# Motor_Power.net
KiCad netlist of a schematic drawn in Altium Designer
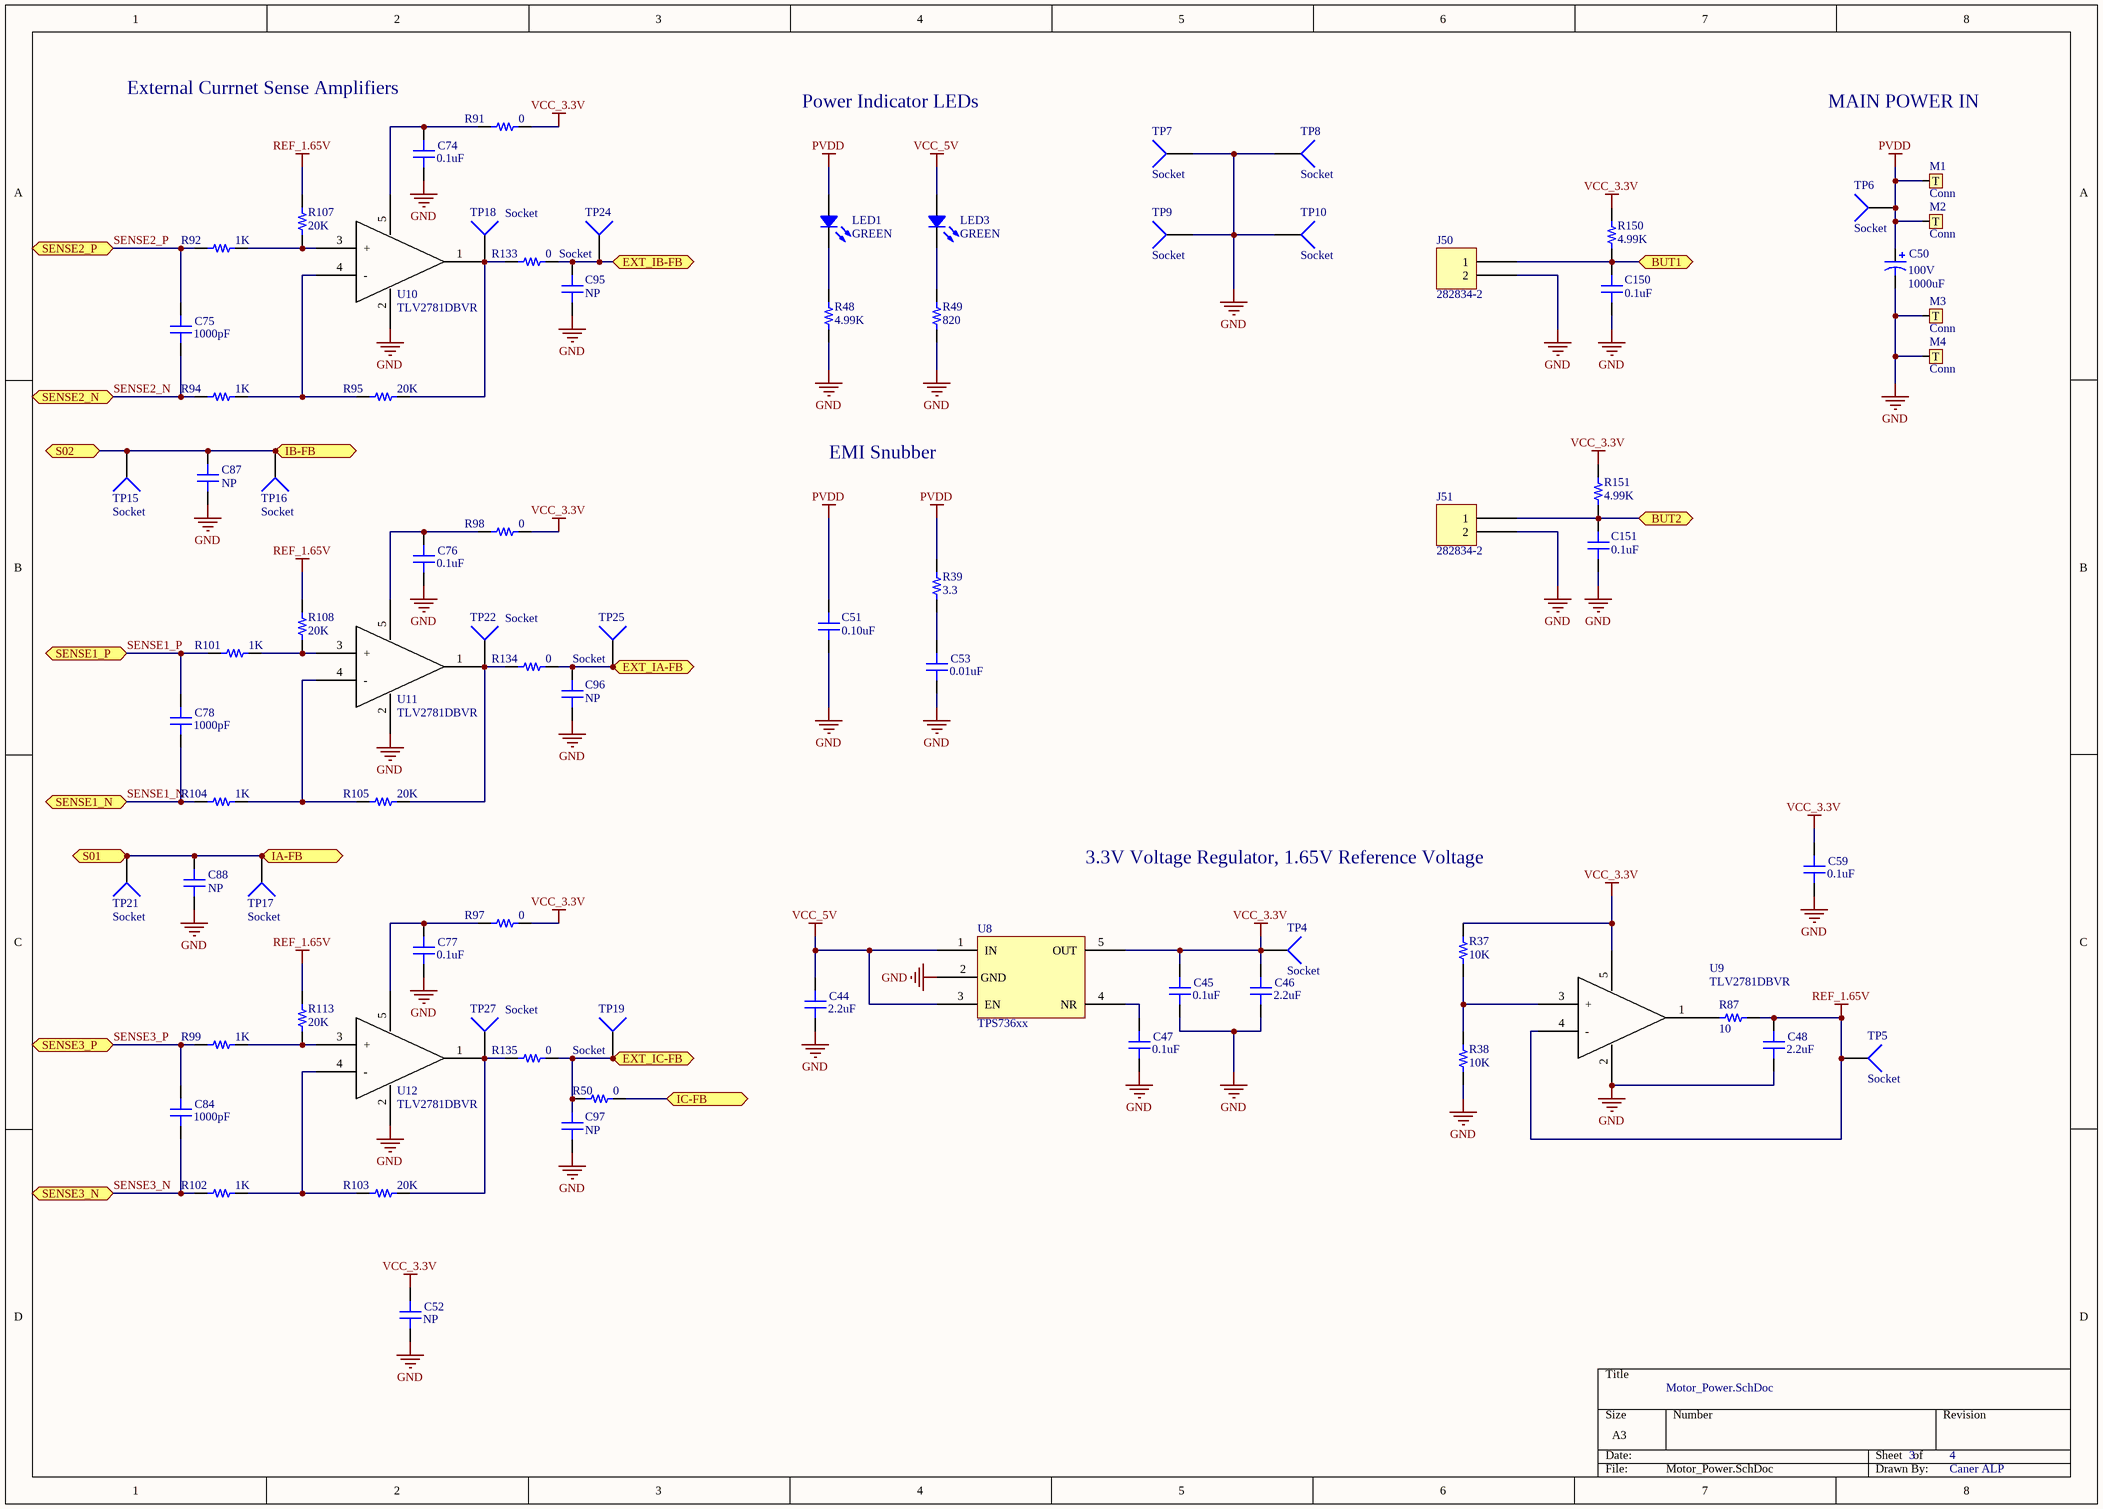
[diagram p0: Motor_Power.SchDoc]

(export (version "E")
  (design (tool "Eeschema 10.0.6"))
  (components
    (comp (ref "C44")
      (value "2.2uF")
      (footprint "CAP 0603/1608")
      (description "CAP CER 0.1UF 16V X7R 0603")
      (fields (field (name "PART NUMBER") "CC0603KPX7R7BB104") (field (name "MANUFACTURER") "Yageo"))
      (libsource (lib "Celestial Library Database") (part "Capacitor"))
    )
    (comp (ref "C45")
      (value "0.1uF")
      (footprint "CAP 0603/1608")
      (description "CAP CER 0.1UF 16V X7R 0603")
      (fields (field (name "PART NUMBER") "CC0603KPX7R7BB104") (field (name "MANUFACTURER") "Yageo"))
      (libsource (lib "Celestial Library Database") (part "Capacitor"))
    )
    (comp (ref "C46")
      (value "2.2uF")
      (footprint "CAP 0603/1608")
      (description "CAP CER 0.1UF 16V X7R 0603")
      (fields (field (name "PART NUMBER") "CC0603KPX7R7BB104") (field (name "MANUFACTURER") "Yageo"))
      (libsource (lib "Celestial Library Database") (part "Capacitor"))
    )
    (comp (ref "C47")
      (value "0.1uF")
      (footprint "CAP 0603/1608")
      (description "CAP CER 0.1UF 16V X7R 0603")
      (fields (field (name "PART NUMBER") "CC0603KPX7R7BB104") (field (name "MANUFACTURER") "Yageo"))
      (libsource (lib "Celestial Library Database") (part "Capacitor"))
    )
    (comp (ref "C48")
      (value "2.2uF")
      (footprint "CAP 0603/1608")
      (description "CAP CER 0.1UF 16V X7R 0603")
      (fields (field (name "PART NUMBER") "CC0603KPX7R7BB104") (field (name "MANUFACTURER") "Yageo"))
      (libsource (lib "Celestial Library Database") (part "Capacitor"))
    )
    (comp (ref "C50")
      (value "100V")
      (footprint "CAPPR7.5-18x35.5")
      (description "Polarized Capacitor (Radial)")
      (fields (field (name "ALTIUM_VALUE") "1000uF") (field (name "PUBLISHER") "Altium Limited"))
      (libsource (lib "Miscellaneous Devices") (part "Cap Pol1"))
    )
    (comp (ref "C51")
      (value "0.10uF")
      (footprint "CAP 0805/2012")
      (description "CAP CER 0.1UF 100V X7R 0805")
      (fields (field (name "PART NUMBER") "C0805C104K1RACTU") (field (name "MANUFACTURER") "Kemet"))
      (libsource (lib "Celestial Library Database") (part "Capacitor"))
    )
    (comp (ref "C52")
      (value "NP")
      (footprint "CAP 0603/1608")
      (description "CAP CER 0.1UF 16V X7R 0603")
      (fields (field (name "PART NUMBER") "CC0603KPX7R7BB104") (field (name "MANUFACTURER") "Yageo"))
      (libsource (lib "Celestial Library Database") (part "Capacitor"))
    )
    (comp (ref "C53")
      (value "0.01uF")
      (footprint "CAP 0603/1608")
      (description "CAP CER 0.1UF 16V X7R 0603")
      (fields (field (name "PART NUMBER") "CC0603KPX7R7BB104") (field (name "MANUFACTURER") "Yageo"))
      (libsource (lib "Celestial Library Database") (part "Capacitor"))
    )
    (comp (ref "C59")
      (value "0.1uF")
      (footprint "CAP 0603/1608")
      (description "CAP CER 0.1UF 16V X7R 0603")
      (fields (field (name "PART NUMBER") "CC0603KPX7R7BB104") (field (name "MANUFACTURER") "Yageo"))
      (libsource (lib "Celestial Library Database") (part "Capacitor"))
    )
    (comp (ref "C74")
      (value "0.1uF")
      (footprint "CAP 0603/1608")
      (description "CAP CER 0.1UF 16V X7R 0603")
      (fields (field (name "PART NUMBER") "CC0603KPX7R7BB104") (field (name "MANUFACTURER") "Yageo"))
      (libsource (lib "Celestial Library Database") (part "Capacitor"))
    )
    (comp (ref "C75")
      (value "1000pF")
      (footprint "CAP 0603/1608")
      (description "CAP CER 0.1UF 16V X7R 0603")
      (fields (field (name "PART NUMBER") "CC0603KPX7R7BB104") (field (name "MANUFACTURER") "Yageo"))
      (libsource (lib "Celestial Library Database") (part "Capacitor"))
    )
    (comp (ref "C76")
      (value "0.1uF")
      (footprint "CAP 0603/1608")
      (description "CAP CER 0.1UF 16V X7R 0603")
      (fields (field (name "PART NUMBER") "CC0603KPX7R7BB104") (field (name "MANUFACTURER") "Yageo"))
      (libsource (lib "Celestial Library Database") (part "Capacitor"))
    )
    (comp (ref "C77")
      (value "0.1uF")
      (footprint "CAP 0603/1608")
      (description "CAP CER 0.1UF 16V X7R 0603")
      (fields (field (name "PART NUMBER") "CC0603KPX7R7BB104") (field (name "MANUFACTURER") "Yageo"))
      (libsource (lib "Celestial Library Database") (part "Capacitor"))
    )
    (comp (ref "C78")
      (value "1000pF")
      (footprint "CAP 0603/1608")
      (description "CAP CER 0.1UF 16V X7R 0603")
      (fields (field (name "PART NUMBER") "CC0603KPX7R7BB104") (field (name "MANUFACTURER") "Yageo"))
      (libsource (lib "Celestial Library Database") (part "Capacitor"))
    )
    (comp (ref "C84")
      (value "1000pF")
      (footprint "CAP 0603/1608")
      (description "CAP CER 0.1UF 16V X7R 0603")
      (fields (field (name "PART NUMBER") "CC0603KPX7R7BB104") (field (name "MANUFACTURER") "Yageo"))
      (libsource (lib "Celestial Library Database") (part "Capacitor"))
    )
    (comp (ref "C87")
      (value "NP")
      (footprint "CAP 0603/1608")
      (description "CAP CER 0.1UF 16V X7R 0603")
      (fields (field (name "PART NUMBER") "CC0603KPX7R7BB104") (field (name "MANUFACTURER") "Yageo"))
      (libsource (lib "Celestial Library Database") (part "Capacitor"))
    )
    (comp (ref "C88")
      (value "NP")
      (footprint "CAP 0603/1608")
      (description "CAP CER 0.1UF 16V X7R 0603")
      (fields (field (name "PART NUMBER") "CC0603KPX7R7BB104") (field (name "MANUFACTURER") "Yageo"))
      (libsource (lib "Celestial Library Database") (part "Capacitor"))
    )
    (comp (ref "C95")
      (value "NP")
      (footprint "CAP 0603/1608")
      (description "CAP CER 0.1UF 16V X7R 0603")
      (fields (field (name "PART NUMBER") "CC0603KPX7R7BB104") (field (name "MANUFACTURER") "Yageo"))
      (libsource (lib "Celestial Library Database") (part "Capacitor"))
    )
    (comp (ref "C96")
      (value "NP")
      (footprint "CAP 0603/1608")
      (description "CAP CER 0.1UF 16V X7R 0603")
      (fields (field (name "PART NUMBER") "CC0603KPX7R7BB104") (field (name "MANUFACTURER") "Yageo"))
      (libsource (lib "Celestial Library Database") (part "Capacitor"))
    )
    (comp (ref "C97")
      (value "NP")
      (footprint "CAP 0603/1608")
      (description "CAP CER 0.1UF 16V X7R 0603")
      (fields (field (name "PART NUMBER") "CC0603KPX7R7BB104") (field (name "MANUFACTURER") "Yageo"))
      (libsource (lib "Celestial Library Database") (part "Capacitor"))
    )
    (comp (ref "C150")
      (value "0.1uF")
      (footprint "CAP 0603/1608")
      (description "CAP CER 0.1UF 16V X7R 0603")
      (fields (field (name "PART NUMBER") "CC0603KPX7R7BB104") (field (name "MANUFACTURER") "Yageo"))
      (libsource (lib "Celestial Library Database") (part "Capacitor"))
    )
    (comp (ref "C151")
      (value "0.1uF")
      (footprint "CAP 0603/1608")
      (description "CAP CER 0.1UF 16V X7R 0603")
      (fields (field (name "PART NUMBER") "CC0603KPX7R7BB104") (field (name "MANUFACTURER") "Yageo"))
      (libsource (lib "Celestial Library Database") (part "Capacitor"))
    )
    (comp (ref "J50")
      (value "282834-2")
      (footprint "TE 282834-2")
      (description "TERM BLOCK 2POS SIDE ENT 2.54MM")
      (fields (field (name "MANUFACTURER") "TE Connectivity AMP Connectors") (field (name "VOLTAGE") "150V"))
      (libsource (lib "Celestial Library Database") (part "2 Pin"))
    )
    (comp (ref "J51")
      (value "282834-2")
      (footprint "TE 282834-2")
      (description "TERM BLOCK 2POS SIDE ENT 2.54MM")
      (fields (field (name "MANUFACTURER") "TE Connectivity AMP Connectors") (field (name "VOLTAGE") "150V"))
      (libsource (lib "Celestial Library Database") (part "2 Pin"))
    )
    (comp (ref "LED1")
      (value "GREEN")
      (footprint "LED 0805/2012 YELLOW")
      (description "LED ORANGE CLEAR 0805 SMD")
      (fields (field (name "PART NUMBER") "LTST-C170KFKT") (field (name "MANUFACTURER") "Lite-On Inc."))
      (libsource (lib "Celestial Library Database") (part "LED"))
    )
    (comp (ref "LED3")
      (value "GREEN")
      (footprint "LED 0805/2012 YELLOW")
      (description "LED ORANGE CLEAR 0805 SMD")
      (fields (field (name "PART NUMBER") "LTST-C170KFKT") (field (name "MANUFACTURER") "Lite-On Inc."))
      (libsource (lib "Celestial Library Database") (part "LED"))
    )
    (comp (ref "M1") (value "Conn") (footprint "M5 Nut") (libsource (lib "Altium Component") (part "1 Conn")))
    (comp (ref "M2") (value "Conn") (footprint "M5 Nut") (libsource (lib "Altium Component") (part "1 Conn")))
    (comp (ref "M3") (value "Conn") (footprint "M5 Nut") (libsource (lib "Altium Component") (part "1 Conn")))
    (comp (ref "M4") (value "Conn") (footprint "M5 Nut") (libsource (lib "Altium Component") (part "1 Conn")))
    (comp (ref "R37")
      (value "10K")
      (footprint "RES 0603/1608")
      (description "RES SMD 330 OHM 5% 1/10W 0603")
      (fields
        (field (name "PART NUMBER") "ERJ-3GEYJ331V")
        (field (name "MANUFACTURER") "Panasonic Electronic Components")
      )
      (libsource (lib "Celestial Library Database") (part "Resistor"))
    )
    (comp (ref "R38")
      (value "10K")
      (footprint "RES 0603/1608")
      (description "RES SMD 330 OHM 5% 1/10W 0603")
      (fields
        (field (name "PART NUMBER") "ERJ-3GEYJ331V")
        (field (name "MANUFACTURER") "Panasonic Electronic Components")
      )
      (libsource (lib "Celestial Library Database") (part "Resistor"))
    )
    (comp (ref "R39")
      (value "3.3")
      (footprint "RES 1206/3216")
      (description "RES SMD 3.3 OHM 5% 1/4W 1206")
      (fields
        (field (name "PART NUMBER") "ERJ-8GEYJ3R3V")
        (field (name "MANUFACTURER") "Panasonic Electronic Components")
      )
      (libsource (lib "Celestial Library Database") (part "Resistor"))
    )
    (comp (ref "R48")
      (value "4.99K")
      (footprint "RES 0603/1608")
      (description "RES SMD 330 OHM 5% 1/10W 0603")
      (fields
        (field (name "PART NUMBER") "ERJ-3GEYJ331V")
        (field (name "MANUFACTURER") "Panasonic Electronic Components")
      )
      (libsource (lib "Celestial Library Database") (part "Resistor"))
    )
    (comp (ref "R49")
      (value "820")
      (footprint "RES 0603/1608")
      (description "RES SMD 330 OHM 5% 1/10W 0603")
      (fields
        (field (name "PART NUMBER") "ERJ-3GEYJ331V")
        (field (name "MANUFACTURER") "Panasonic Electronic Components")
      )
      (libsource (lib "Celestial Library Database") (part "Resistor"))
    )
    (comp (ref "R50")
      (value "0")
      (footprint "RES 0603/1608")
      (description "RES SMD 330 OHM 5% 1/10W 0603")
      (fields
        (field (name "PART NUMBER") "ERJ-3GEYJ331V")
        (field (name "MANUFACTURER") "Panasonic Electronic Components")
      )
      (libsource (lib "Celestial Library Database") (part "Resistor"))
    )
    (comp (ref "R87")
      (value "10")
      (footprint "RES 0603/1608")
      (description "RES SMD 330 OHM 5% 1/10W 0603")
      (fields
        (field (name "PART NUMBER") "ERJ-3GEYJ331V")
        (field (name "MANUFACTURER") "Panasonic Electronic Components")
      )
      (libsource (lib "Celestial Library Database") (part "Resistor"))
    )
    (comp (ref "R91")
      (value "0")
      (footprint "RES 0603/1608")
      (description "RES SMD 330 OHM 5% 1/10W 0603")
      (fields
        (field (name "PART NUMBER") "ERJ-3GEYJ331V")
        (field (name "MANUFACTURER") "Panasonic Electronic Components")
      )
      (libsource (lib "Celestial Library Database") (part "Resistor"))
    )
    (comp (ref "R92")
      (value "1K")
      (footprint "RES 0603/1608")
      (description "RES SMD 330 OHM 5% 1/10W 0603")
      (fields
        (field (name "PART NUMBER") "ERJ-3GEYJ331V")
        (field (name "MANUFACTURER") "Panasonic Electronic Components")
      )
      (libsource (lib "Celestial Library Database") (part "Resistor"))
    )
    (comp (ref "R94")
      (value "1K")
      (footprint "RES 0603/1608")
      (description "RES SMD 330 OHM 5% 1/10W 0603")
      (fields
        (field (name "PART NUMBER") "ERJ-3GEYJ331V")
        (field (name "MANUFACTURER") "Panasonic Electronic Components")
      )
      (libsource (lib "Celestial Library Database") (part "Resistor"))
    )
    (comp (ref "R95")
      (value "20K")
      (footprint "RES 0603/1608")
      (description "RES SMD 330 OHM 5% 1/10W 0603")
      (fields
        (field (name "PART NUMBER") "ERJ-3GEYJ331V")
        (field (name "MANUFACTURER") "Panasonic Electronic Components")
      )
      (libsource (lib "Celestial Library Database") (part "Resistor"))
    )
    (comp (ref "R97")
      (value "0")
      (footprint "RES 0603/1608")
      (description "RES SMD 330 OHM 5% 1/10W 0603")
      (fields
        (field (name "PART NUMBER") "ERJ-3GEYJ331V")
        (field (name "MANUFACTURER") "Panasonic Electronic Components")
      )
      (libsource (lib "Celestial Library Database") (part "Resistor"))
    )
    (comp (ref "R98")
      (value "0")
      (footprint "RES 0603/1608")
      (description "RES SMD 330 OHM 5% 1/10W 0603")
      (fields
        (field (name "PART NUMBER") "ERJ-3GEYJ331V")
        (field (name "MANUFACTURER") "Panasonic Electronic Components")
      )
      (libsource (lib "Celestial Library Database") (part "Resistor"))
    )
    (comp (ref "R99")
      (value "1K")
      (footprint "RES 0603/1608")
      (description "RES SMD 330 OHM 5% 1/10W 0603")
      (fields
        (field (name "PART NUMBER") "ERJ-3GEYJ331V")
        (field (name "MANUFACTURER") "Panasonic Electronic Components")
      )
      (libsource (lib "Celestial Library Database") (part "Resistor"))
    )
    (comp (ref "R101")
      (value "1K")
      (footprint "RES 0603/1608")
      (description "RES SMD 330 OHM 5% 1/10W 0603")
      (fields
        (field (name "PART NUMBER") "ERJ-3GEYJ331V")
        (field (name "MANUFACTURER") "Panasonic Electronic Components")
      )
      (libsource (lib "Celestial Library Database") (part "Resistor"))
    )
    (comp (ref "R102")
      (value "1K")
      (footprint "RES 0603/1608")
      (description "RES SMD 330 OHM 5% 1/10W 0603")
      (fields
        (field (name "PART NUMBER") "ERJ-3GEYJ331V")
        (field (name "MANUFACTURER") "Panasonic Electronic Components")
      )
      (libsource (lib "Celestial Library Database") (part "Resistor"))
    )
    (comp (ref "R103")
      (value "20K")
      (footprint "RES 0603/1608")
      (description "RES SMD 330 OHM 5% 1/10W 0603")
      (fields
        (field (name "PART NUMBER") "ERJ-3GEYJ331V")
        (field (name "MANUFACTURER") "Panasonic Electronic Components")
      )
      (libsource (lib "Celestial Library Database") (part "Resistor"))
    )
    (comp (ref "R104")
      (value "1K")
      (footprint "RES 0603/1608")
      (description "RES SMD 330 OHM 5% 1/10W 0603")
      (fields
        (field (name "PART NUMBER") "ERJ-3GEYJ331V")
        (field (name "MANUFACTURER") "Panasonic Electronic Components")
      )
      (libsource (lib "Celestial Library Database") (part "Resistor"))
    )
    (comp (ref "R105")
      (value "20K")
      (footprint "RES 0603/1608")
      (description "RES SMD 330 OHM 5% 1/10W 0603")
      (fields
        (field (name "PART NUMBER") "ERJ-3GEYJ331V")
        (field (name "MANUFACTURER") "Panasonic Electronic Components")
      )
      (libsource (lib "Celestial Library Database") (part "Resistor"))
    )
    (comp (ref "R107")
      (value "20K")
      (footprint "RES 0603/1608")
      (description "RES SMD 330 OHM 5% 1/10W 0603")
      (fields
        (field (name "PART NUMBER") "ERJ-3GEYJ331V")
        (field (name "MANUFACTURER") "Panasonic Electronic Components")
      )
      (libsource (lib "Celestial Library Database") (part "Resistor"))
    )
    (comp (ref "R108")
      (value "20K")
      (footprint "RES 0603/1608")
      (description "RES SMD 330 OHM 5% 1/10W 0603")
      (fields
        (field (name "PART NUMBER") "ERJ-3GEYJ331V")
        (field (name "MANUFACTURER") "Panasonic Electronic Components")
      )
      (libsource (lib "Celestial Library Database") (part "Resistor"))
    )
    (comp (ref "R113")
      (value "20K")
      (footprint "RES 0603/1608")
      (description "RES SMD 330 OHM 5% 1/10W 0603")
      (fields
        (field (name "PART NUMBER") "ERJ-3GEYJ331V")
        (field (name "MANUFACTURER") "Panasonic Electronic Components")
      )
      (libsource (lib "Celestial Library Database") (part "Resistor"))
    )
    (comp (ref "R133")
      (value "0")
      (footprint "RES 0603/1608")
      (description "RES SMD 330 OHM 5% 1/10W 0603")
      (fields
        (field (name "PART NUMBER") "ERJ-3GEYJ331V")
        (field (name "MANUFACTURER") "Panasonic Electronic Components")
      )
      (libsource (lib "Celestial Library Database") (part "Resistor"))
    )
    (comp (ref "R134")
      (value "0")
      (footprint "RES 0603/1608")
      (description "RES SMD 330 OHM 5% 1/10W 0603")
      (fields
        (field (name "PART NUMBER") "ERJ-3GEYJ331V")
        (field (name "MANUFACTURER") "Panasonic Electronic Components")
      )
      (libsource (lib "Celestial Library Database") (part "Resistor"))
    )
    (comp (ref "R135")
      (value "0")
      (footprint "RES 0603/1608")
      (description "RES SMD 330 OHM 5% 1/10W 0603")
      (fields
        (field (name "PART NUMBER") "ERJ-3GEYJ331V")
        (field (name "MANUFACTURER") "Panasonic Electronic Components")
      )
      (libsource (lib "Celestial Library Database") (part "Resistor"))
    )
    (comp (ref "R150")
      (value "4.99K")
      (footprint "RES 0603/1608")
      (description "RES SMD 330 OHM 5% 1/10W 0603")
      (fields
        (field (name "PART NUMBER") "ERJ-3GEYJ331V")
        (field (name "MANUFACTURER") "Panasonic Electronic Components")
      )
      (libsource (lib "Celestial Library Database") (part "Resistor"))
    )
    (comp (ref "R151")
      (value "4.99K")
      (footprint "RES 0603/1608")
      (description "RES SMD 330 OHM 5% 1/10W 0603")
      (fields
        (field (name "PART NUMBER") "ERJ-3GEYJ331V")
        (field (name "MANUFACTURER") "Panasonic Electronic Components")
      )
      (libsource (lib "Celestial Library Database") (part "Resistor"))
    )
    (comp (ref "TP4")
      (value "Socket")
      (footprint "PIN1")
      (fields (field (name "PUBLISHER") "Altium Limited"))
      (libsource (lib "Miscellaneous Connectors") (part "Socket"))
    )
    (comp (ref "TP5")
      (value "Socket")
      (footprint "PIN1")
      (fields (field (name "PUBLISHER") "Altium Limited"))
      (libsource (lib "Miscellaneous Connectors") (part "Socket"))
    )
    (comp (ref "TP6")
      (value "Socket")
      (footprint "PIN1")
      (fields (field (name "PUBLISHER") "Altium Limited"))
      (libsource (lib "Miscellaneous Connectors") (part "Socket"))
    )
    (comp (ref "TP7")
      (value "Socket")
      (footprint "PIN1")
      (fields (field (name "PUBLISHER") "Altium Limited"))
      (libsource (lib "Miscellaneous Connectors") (part "Socket"))
    )
    (comp (ref "TP8")
      (value "Socket")
      (footprint "PIN1")
      (fields (field (name "PUBLISHER") "Altium Limited"))
      (libsource (lib "Miscellaneous Connectors") (part "Socket"))
    )
    (comp (ref "TP9")
      (value "Socket")
      (footprint "PIN1")
      (fields (field (name "PUBLISHER") "Altium Limited"))
      (libsource (lib "Miscellaneous Connectors") (part "Socket"))
    )
    (comp (ref "TP10")
      (value "Socket")
      (footprint "PIN1")
      (fields (field (name "PUBLISHER") "Altium Limited"))
      (libsource (lib "Miscellaneous Connectors") (part "Socket"))
    )
    (comp (ref "TP15")
      (value "Socket")
      (footprint "PIN1")
      (fields (field (name "PUBLISHER") "Altium Limited"))
      (libsource (lib "Miscellaneous Connectors") (part "Socket"))
    )
    (comp (ref "TP16")
      (value "Socket")
      (footprint "PIN1")
      (fields (field (name "PUBLISHER") "Altium Limited"))
      (libsource (lib "Miscellaneous Connectors") (part "Socket"))
    )
    (comp (ref "TP17")
      (value "Socket")
      (footprint "PIN1")
      (fields (field (name "PUBLISHER") "Altium Limited"))
      (libsource (lib "Miscellaneous Connectors") (part "Socket"))
    )
    (comp (ref "TP18")
      (value "Socket")
      (footprint "PIN1")
      (fields (field (name "PUBLISHER") "Altium Limited"))
      (libsource (lib "Miscellaneous Connectors") (part "Socket"))
    )
    (comp (ref "TP19")
      (value "Socket")
      (footprint "PIN1")
      (fields (field (name "PUBLISHER") "Altium Limited"))
      (libsource (lib "Miscellaneous Connectors") (part "Socket"))
    )
    (comp (ref "TP21")
      (value "Socket")
      (footprint "PIN1")
      (fields (field (name "PUBLISHER") "Altium Limited"))
      (libsource (lib "Miscellaneous Connectors") (part "Socket"))
    )
    (comp (ref "TP22")
      (value "Socket")
      (footprint "PIN1")
      (fields (field (name "PUBLISHER") "Altium Limited"))
      (libsource (lib "Miscellaneous Connectors") (part "Socket"))
    )
    (comp (ref "TP24")
      (value "Socket")
      (footprint "PIN1")
      (fields (field (name "PUBLISHER") "Altium Limited"))
      (libsource (lib "Miscellaneous Connectors") (part "Socket"))
    )
    (comp (ref "TP25")
      (value "Socket")
      (footprint "PIN1")
      (fields (field (name "PUBLISHER") "Altium Limited"))
      (libsource (lib "Miscellaneous Connectors") (part "Socket"))
    )
    (comp (ref "TP27")
      (value "Socket")
      (footprint "PIN1")
      (fields (field (name "PUBLISHER") "Altium Limited"))
      (libsource (lib "Miscellaneous Connectors") (part "Socket"))
    )
    (comp (ref "U8")
      (value "TPS736xx")
      (footprint "DBV005")
      (description "LDO")
      (libsource (lib "Altium Component") (part "TPS736xx"))
    )
    (comp (ref "U9")
      (value "TLV2781DBVR")
      (footprint "DBV005")
      (libsource (lib "Altium Component") (part "TLV2781DBVR"))
    )
    (comp (ref "U10")
      (value "TLV2781DBVR")
      (footprint "DBV005")
      (libsource (lib "Altium Component") (part "TLV2781DBVR"))
    )
    (comp (ref "U11")
      (value "TLV2781DBVR")
      (footprint "DBV005")
      (libsource (lib "Altium Component") (part "TLV2781DBVR"))
    )
    (comp (ref "U12")
      (value "TLV2781DBVR")
      (footprint "DBV005")
      (libsource (lib "Altium Component") (part "TLV2781DBVR"))
    )
  )
  (nets
    (net (code "1") (name "/BUT1") (class "Default")
      (node (ref "C150") (pin "2") (pinfunction "2_2") (pintype "passive"))
      (node (ref "J50") (pin "1") (pinfunction "1_1") (pintype "passive"))
      (node (ref "R150") (pin "1") (pinfunction "1_1") (pintype "passive"))
    )
    (net (code "2") (name "/BUT2") (class "Default")
      (node (ref "C151") (pin "2") (pinfunction "2_2") (pintype "passive"))
      (node (ref "J51") (pin "1") (pinfunction "1_1") (pintype "passive"))
      (node (ref "R151") (pin "1") (pinfunction "1_1") (pintype "passive"))
    )
    (net (code "3") (name "/EXT_IA-FB") (class "Default")
      (node (ref "C96") (pin "2") (pinfunction "2_2") (pintype "passive"))
      (node (ref "R134") (pin "1") (pinfunction "1_1") (pintype "passive"))
      (node (ref "TP25") (pin "1") (pinfunction "1_1") (pintype "passive"))
    )
    (net (code "4") (name "/EXT_IB-FB") (class "Default")
      (node (ref "C95") (pin "2") (pinfunction "2_2") (pintype "passive"))
      (node (ref "R133") (pin "1") (pinfunction "1_1") (pintype "passive"))
      (node (ref "TP24") (pin "1") (pinfunction "1_1") (pintype "passive"))
    )
    (net (code "5") (name "/EXT_IC-FB") (class "Default")
      (node (ref "C97") (pin "2") (pinfunction "2_2") (pintype "passive"))
      (node (ref "R135") (pin "1") (pinfunction "1_1") (pintype "passive"))
      (node (ref "R50") (pin "2") (pinfunction "2_2") (pintype "passive"))
      (node (ref "TP19") (pin "1") (pinfunction "1_1") (pintype "passive"))
    )
    (net (code "6") (name "/IA-FB") (class "Default")
      (node (ref "C88") (pin "2") (pinfunction "2_2") (pintype "passive"))
      (node (ref "TP17") (pin "1") (pinfunction "1_1") (pintype "passive"))
      (node (ref "TP21") (pin "1") (pinfunction "1_1") (pintype "passive"))
    )
    (net (code "7") (name "/IB-FB") (class "Default")
      (node (ref "C87") (pin "2") (pinfunction "2_2") (pintype "passive"))
      (node (ref "TP15") (pin "1") (pinfunction "1_1") (pintype "passive"))
      (node (ref "TP16") (pin "1") (pinfunction "1_1") (pintype "passive"))
    )
    (net (code "8") (name "/IC-FB") (class "Default")
      (node (ref "R50") (pin "1") (pinfunction "1_1") (pintype "passive"))
    )
    (net (code "9") (name "/SENSE1_N") (class "Default")
      (node (ref "C78") (pin "1") (pinfunction "1_1") (pintype "passive"))
      (node (ref "R104") (pin "2") (pinfunction "2_2") (pintype "passive"))
    )
    (net (code "10") (name "/SENSE1_P") (class "Default")
      (node (ref "C78") (pin "2") (pinfunction "2_2") (pintype "passive"))
      (node (ref "R101") (pin "2") (pinfunction "2_2") (pintype "passive"))
    )
    (net (code "11") (name "/SENSE2_N") (class "Default")
      (node (ref "C75") (pin "1") (pinfunction "1_1") (pintype "passive"))
      (node (ref "R94") (pin "2") (pinfunction "2_2") (pintype "passive"))
    )
    (net (code "12") (name "/SENSE2_P") (class "Default")
      (node (ref "C75") (pin "2") (pinfunction "2_2") (pintype "passive"))
      (node (ref "R92") (pin "2") (pinfunction "2_2") (pintype "passive"))
    )
    (net (code "13") (name "/SENSE3_N") (class "Default")
      (node (ref "C84") (pin "1") (pinfunction "1_1") (pintype "passive"))
      (node (ref "R102") (pin "2") (pinfunction "2_2") (pintype "passive"))
    )
    (net (code "14") (name "/SENSE3_P") (class "Default")
      (node (ref "C84") (pin "2") (pinfunction "2_2") (pintype "passive"))
      (node (ref "R99") (pin "2") (pinfunction "2_2") (pintype "passive"))
    )
    (net (code "15") (name "GND") (class "Default")
      (node (ref "C150") (pin "1") (pinfunction "1_1") (pintype "passive"))
      (node (ref "C151") (pin "1") (pinfunction "1_1") (pintype "passive"))
      (node (ref "C44") (pin "1") (pinfunction "1_1") (pintype "passive"))
      (node (ref "C45") (pin "1") (pinfunction "1_1") (pintype "passive"))
      (node (ref "C46") (pin "1") (pinfunction "1_1") (pintype "passive"))
      (node (ref "C47") (pin "1") (pinfunction "1_1") (pintype "passive"))
      (node (ref "C48") (pin "1") (pinfunction "1_1") (pintype "passive"))
      (node (ref "C50") (pin "2") (pinfunction "2_2") (pintype "passive"))
      (node (ref "C51") (pin "1") (pinfunction "1_1") (pintype "passive"))
      (node (ref "C52") (pin "1") (pinfunction "1_1") (pintype "passive"))
      (node (ref "C53") (pin "1") (pinfunction "1_1") (pintype "passive"))
      (node (ref "C59") (pin "1") (pinfunction "1_1") (pintype "passive"))
      (node (ref "C74") (pin "1") (pinfunction "1_1") (pintype "passive"))
      (node (ref "C76") (pin "1") (pinfunction "1_1") (pintype "passive"))
      (node (ref "C77") (pin "1") (pinfunction "1_1") (pintype "passive"))
      (node (ref "C87") (pin "1") (pinfunction "1_1") (pintype "passive"))
      (node (ref "C88") (pin "1") (pinfunction "1_1") (pintype "passive"))
      (node (ref "C95") (pin "1") (pinfunction "1_1") (pintype "passive"))
      (node (ref "C96") (pin "1") (pinfunction "1_1") (pintype "passive"))
      (node (ref "C97") (pin "1") (pinfunction "1_1") (pintype "passive"))
      (node (ref "J50") (pin "2") (pinfunction "2_2") (pintype "passive"))
      (node (ref "J51") (pin "2") (pinfunction "2_2") (pintype "passive"))
      (node (ref "M3") (pin "1") (pinfunction "T_1") (pintype "passive"))
      (node (ref "M4") (pin "1") (pinfunction "T_1") (pintype "passive"))
      (node (ref "R38") (pin "2") (pinfunction "2_2") (pintype "passive"))
      (node (ref "R48") (pin "1") (pinfunction "1_1") (pintype "passive"))
      (node (ref "R49") (pin "1") (pinfunction "1_1") (pintype "passive"))
      (node (ref "TP10") (pin "1") (pinfunction "1_1") (pintype "passive"))
      (node (ref "TP7") (pin "1") (pinfunction "1_1") (pintype "passive"))
      (node (ref "TP8") (pin "1") (pinfunction "1_1") (pintype "passive"))
      (node (ref "TP9") (pin "1") (pinfunction "1_1") (pintype "passive"))
      (node (ref "U10") (pin "2") (pinfunction "2_2") (pintype "passive"))
      (node (ref "U11") (pin "2") (pinfunction "2_2") (pintype "passive"))
      (node (ref "U12") (pin "2") (pinfunction "2_2") (pintype "passive"))
      (node (ref "U8") (pin "2") (pinfunction "GND_2") (pintype "passive"))
      (node (ref "U9") (pin "2") (pinfunction "2_2") (pintype "passive"))
    )
    (net (code "16") (name "Net-(C53-Pad2)") (class "Default")
      (node (ref "C53") (pin "2") (pinfunction "2_2") (pintype "passive"))
      (node (ref "R39") (pin "1") (pinfunction "1_1") (pintype "passive"))
    )
    (net (code "17") (name "Net-(C74-Pad2)") (class "Default")
      (node (ref "C74") (pin "2") (pinfunction "2_2") (pintype "passive"))
      (node (ref "R91") (pin "2") (pinfunction "2_2") (pintype "passive"))
      (node (ref "U10") (pin "5") (pinfunction "5_5") (pintype "passive"))
    )
    (net (code "18") (name "Net-(C76-Pad2)") (class "Default")
      (node (ref "C76") (pin "2") (pinfunction "2_2") (pintype "passive"))
      (node (ref "R98") (pin "2") (pinfunction "2_2") (pintype "passive"))
      (node (ref "U11") (pin "5") (pinfunction "5_5") (pintype "passive"))
    )
    (net (code "19") (name "Net-(C77-Pad2)") (class "Default")
      (node (ref "C77") (pin "2") (pinfunction "2_2") (pintype "passive"))
      (node (ref "R97") (pin "2") (pinfunction "2_2") (pintype "passive"))
      (node (ref "U12") (pin "5") (pinfunction "5_5") (pintype "passive"))
    )
    (net (code "20") (name "Net-(LED1-Pad2)") (class "Default")
      (node (ref "LED1") (pin "2") (pinfunction "2_2") (pintype "passive"))
      (node (ref "R48") (pin "2") (pinfunction "2_2") (pintype "passive"))
    )
    (net (code "21") (name "Net-(LED3-Pad2)") (class "Default")
      (node (ref "LED3") (pin "2") (pinfunction "2_2") (pintype "passive"))
      (node (ref "R49") (pin "2") (pinfunction "2_2") (pintype "passive"))
    )
    (net (code "22") (name "Net-(R87-Pad1)") (class "Default")
      (node (ref "R87") (pin "1") (pinfunction "1_1") (pintype "passive"))
      (node (ref "U9") (pin "1") (pinfunction "1_1") (pintype "passive"))
    )
    (net (code "23") (name "Net-(R103-Pad1)") (class "Default")
      (node (ref "R103") (pin "1") (pinfunction "1_1") (pintype "passive"))
      (node (ref "R135") (pin "2") (pinfunction "2_2") (pintype "passive"))
      (node (ref "TP27") (pin "1") (pinfunction "1_1") (pintype "passive"))
      (node (ref "U12") (pin "1") (pinfunction "1_1") (pintype "passive"))
    )
    (net (code "24") (name "Net-(R105-Pad1)") (class "Default")
      (node (ref "R105") (pin "1") (pinfunction "1_1") (pintype "passive"))
      (node (ref "R134") (pin "2") (pinfunction "2_2") (pintype "passive"))
      (node (ref "TP22") (pin "1") (pinfunction "1_1") (pintype "passive"))
      (node (ref "U11") (pin "1") (pinfunction "1_1") (pintype "passive"))
    )
    (net (code "25") (name "Net-(R133-Pad2)") (class "Default")
      (node (ref "R133") (pin "2") (pinfunction "2_2") (pintype "passive"))
      (node (ref "R95") (pin "1") (pinfunction "1_1") (pintype "passive"))
      (node (ref "TP18") (pin "1") (pinfunction "1_1") (pintype "passive"))
      (node (ref "U10") (pin "1") (pinfunction "1_1") (pintype "passive"))
    )
    (net (code "26") (name "Net-(U8-NR)") (class "Default")
      (node (ref "C47") (pin "2") (pinfunction "2_2") (pintype "passive"))
      (node (ref "U8") (pin "4") (pinfunction "NR_4") (pintype "passive"))
    )
    (net (code "27") (name "Net-(U9-+)") (class "Default")
      (node (ref "R37") (pin "2") (pinfunction "2_2") (pintype "passive"))
      (node (ref "R38") (pin "1") (pinfunction "1_1") (pintype "passive"))
      (node (ref "U9") (pin "3") (pinfunction "+_3") (pintype "passive"))
    )
    (net (code "28") (name "Net-(U10-+)") (class "Default")
      (node (ref "R107") (pin "2") (pinfunction "2_2") (pintype "passive"))
      (node (ref "R92") (pin "1") (pinfunction "1_1") (pintype "passive"))
      (node (ref "U10") (pin "3") (pinfunction "+_3") (pintype "passive"))
    )
    (net (code "29") (name "Net-(U10--)") (class "Default")
      (node (ref "R94") (pin "1") (pinfunction "1_1") (pintype "passive"))
      (node (ref "R95") (pin "2") (pinfunction "2_2") (pintype "passive"))
      (node (ref "U10") (pin "4") (pinfunction "-_4") (pintype "passive"))
    )
    (net (code "30") (name "Net-(U11-+)") (class "Default")
      (node (ref "R101") (pin "1") (pinfunction "1_1") (pintype "passive"))
      (node (ref "R108") (pin "2") (pinfunction "2_2") (pintype "passive"))
      (node (ref "U11") (pin "3") (pinfunction "+_3") (pintype "passive"))
    )
    (net (code "31") (name "Net-(U11--)") (class "Default")
      (node (ref "R104") (pin "1") (pinfunction "1_1") (pintype "passive"))
      (node (ref "R105") (pin "2") (pinfunction "2_2") (pintype "passive"))
      (node (ref "U11") (pin "4") (pinfunction "-_4") (pintype "passive"))
    )
    (net (code "32") (name "Net-(U12-+)") (class "Default")
      (node (ref "R113") (pin "2") (pinfunction "2_2") (pintype "passive"))
      (node (ref "R99") (pin "1") (pinfunction "1_1") (pintype "passive"))
      (node (ref "U12") (pin "3") (pinfunction "+_3") (pintype "passive"))
    )
    (net (code "33") (name "Net-(U12--)") (class "Default")
      (node (ref "R102") (pin "1") (pinfunction "1_1") (pintype "passive"))
      (node (ref "R103") (pin "2") (pinfunction "2_2") (pintype "passive"))
      (node (ref "U12") (pin "4") (pinfunction "-_4") (pintype "passive"))
    )
    (net (code "34") (name "PVDD") (class "Default")
      (node (ref "C50") (pin "1") (pinfunction "1_1") (pintype "passive"))
      (node (ref "C51") (pin "2") (pinfunction "2_2") (pintype "passive"))
      (node (ref "LED1") (pin "1") (pinfunction "1_1") (pintype "passive"))
      (node (ref "M1") (pin "1") (pinfunction "T_1") (pintype "passive"))
      (node (ref "M2") (pin "1") (pinfunction "T_1") (pintype "passive"))
      (node (ref "R39") (pin "2") (pinfunction "2_2") (pintype "passive"))
      (node (ref "TP6") (pin "1") (pinfunction "1_1") (pintype "passive"))
    )
    (net (code "35") (name "REF_1.65V") (class "Default")
      (node (ref "C48") (pin "2") (pinfunction "2_2") (pintype "passive"))
      (node (ref "R107") (pin "1") (pinfunction "1_1") (pintype "passive"))
      (node (ref "R108") (pin "1") (pinfunction "1_1") (pintype "passive"))
      (node (ref "R113") (pin "1") (pinfunction "1_1") (pintype "passive"))
      (node (ref "R87") (pin "2") (pinfunction "2_2") (pintype "passive"))
      (node (ref "TP5") (pin "1") (pinfunction "1_1") (pintype "passive"))
      (node (ref "U9") (pin "4") (pinfunction "-_4") (pintype "passive"))
    )
    (net (code "36") (name "VCC_3.3V") (class "Default")
      (node (ref "C45") (pin "2") (pinfunction "2_2") (pintype "passive"))
      (node (ref "C46") (pin "2") (pinfunction "2_2") (pintype "passive"))
      (node (ref "C52") (pin "2") (pinfunction "2_2") (pintype "passive"))
      (node (ref "C59") (pin "2") (pinfunction "2_2") (pintype "passive"))
      (node (ref "R150") (pin "2") (pinfunction "2_2") (pintype "passive"))
      (node (ref "R151") (pin "2") (pinfunction "2_2") (pintype "passive"))
      (node (ref "R37") (pin "1") (pinfunction "1_1") (pintype "passive"))
      (node (ref "R91") (pin "1") (pinfunction "1_1") (pintype "passive"))
      (node (ref "R97") (pin "1") (pinfunction "1_1") (pintype "passive"))
      (node (ref "R98") (pin "1") (pinfunction "1_1") (pintype "passive"))
      (node (ref "TP4") (pin "1") (pinfunction "1_1") (pintype "passive"))
      (node (ref "U8") (pin "5") (pinfunction "OUT_5") (pintype "passive"))
      (node (ref "U9") (pin "5") (pinfunction "5_5") (pintype "passive"))
    )
    (net (code "37") (name "VCC_5V") (class "Default")
      (node (ref "C44") (pin "2") (pinfunction "2_2") (pintype "passive"))
      (node (ref "LED3") (pin "1") (pinfunction "1_1") (pintype "passive"))
      (node (ref "U8") (pin "1") (pinfunction "IN_1") (pintype "passive"))
      (node (ref "U8") (pin "3") (pinfunction "EN_3") (pintype "passive"))
    )
  )
)
